# PATHOS_SOM_CAN.net
KiCad netlist of a schematic drawn in Altium Designer
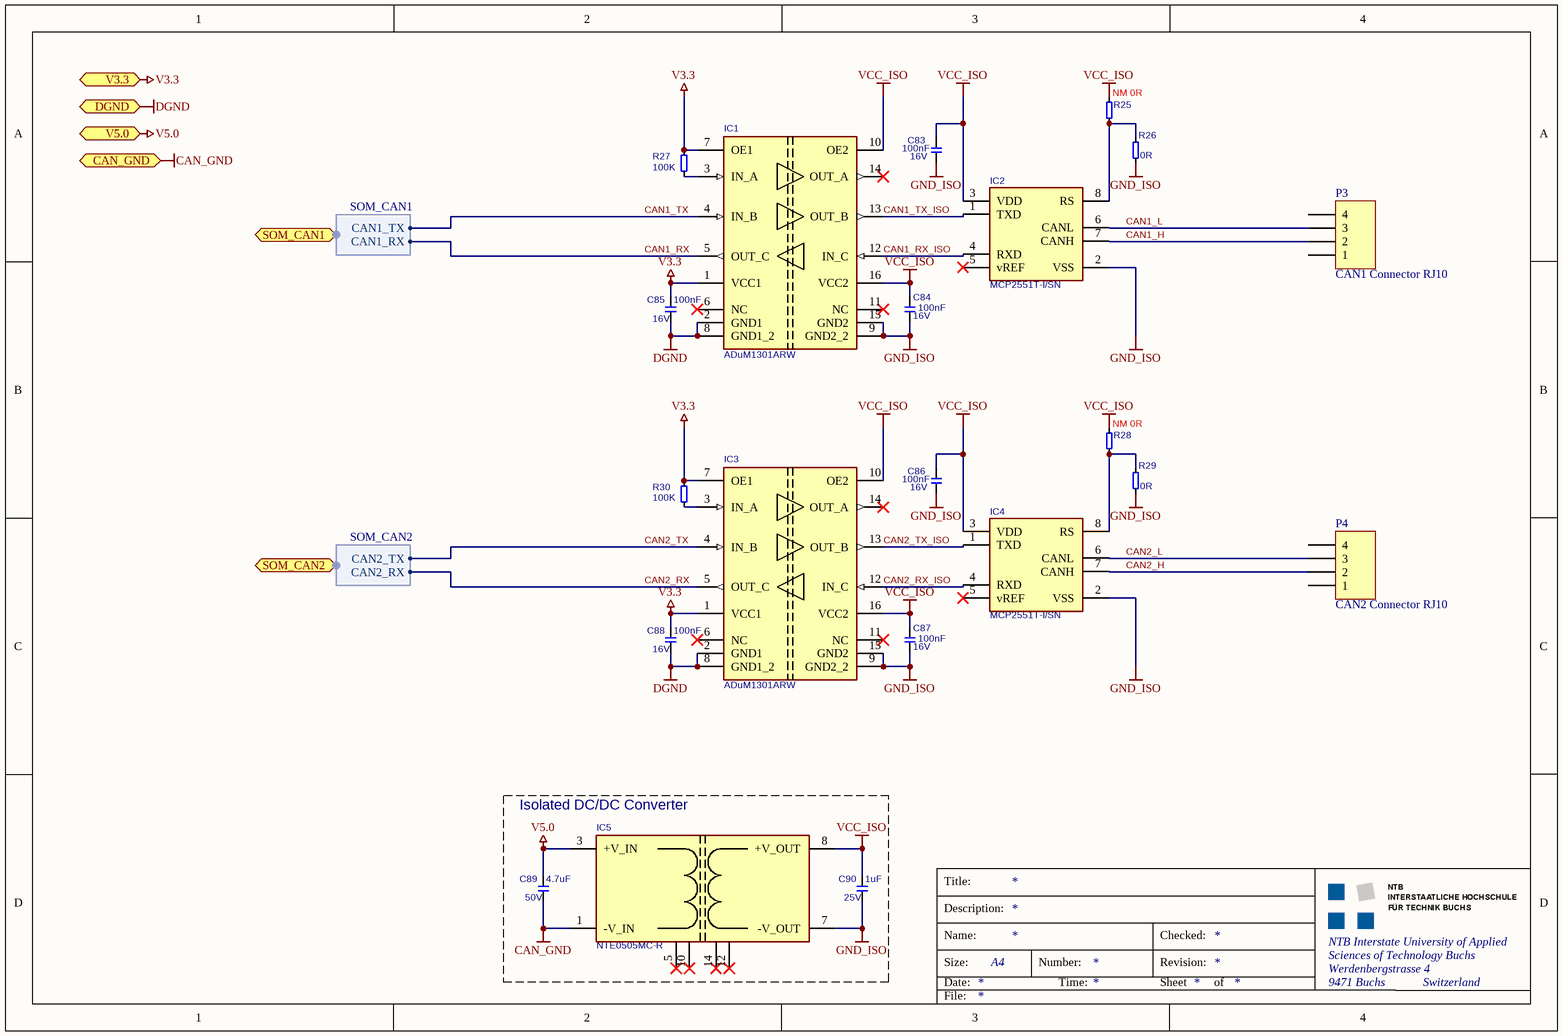
[diagram p0: PATHOS_SOM_CAN.SchDoc]

(export (version "E")
  (design (tool "Eeschema 10.0.6"))
  (components
    (comp (ref "C83")
      (value "100nF")
      (footprint "0603_3D")
      (description "Capacitor Ceramic X7R 100nF 16V 10% 0603")
      (fields (field (name "TOLERANCE") "10%") (field (name "RATING") "16V"))
      (libsource (lib "Evaluation Board") (part "C-X7R-100nF-16V-10%-0603"))
    )
    (comp (ref "C84")
      (value "100nF")
      (footprint "0603_3D")
      (description "Capacitor Ceramic X7R 100nF 16V 10% 0603")
      (fields (field (name "TOLERANCE") "10%") (field (name "RATING") "16V"))
      (libsource (lib "Evaluation Board") (part "C-X7R-100nF-16V-10%-0603"))
    )
    (comp (ref "C85")
      (value "100nF")
      (footprint "0603_3D")
      (description "Capacitor Ceramic X7R 100nF 16V 10% 0603")
      (fields (field (name "TOLERANCE") "10%") (field (name "RATING") "16V"))
      (libsource (lib "Evaluation Board") (part "C-X7R-100nF-16V-10%-0603"))
    )
    (comp (ref "C86")
      (value "100nF")
      (footprint "0603_3D")
      (description "Capacitor Ceramic X7R 100nF 16V 10% 0603")
      (fields (field (name "TOLERANCE") "10%") (field (name "RATING") "16V"))
      (libsource (lib "Evaluation Board") (part "C-X7R-100nF-16V-10%-0603"))
    )
    (comp (ref "C87")
      (value "100nF")
      (footprint "0603_3D")
      (description "Capacitor Ceramic X7R 100nF 16V 10% 0603")
      (fields (field (name "TOLERANCE") "10%") (field (name "RATING") "16V"))
      (libsource (lib "Evaluation Board") (part "C-X7R-100nF-16V-10%-0603"))
    )
    (comp (ref "C88")
      (value "100nF")
      (footprint "0603_3D")
      (description "Capacitor Ceramic X7R 100nF 16V 10% 0603")
      (fields (field (name "TOLERANCE") "10%") (field (name "RATING") "16V"))
      (libsource (lib "Evaluation Board") (part "C-X7R-100nF-16V-10%-0603"))
    )
    (comp (ref "C89")
      (value "4.7uF")
      (footprint "1206")
      (description "Capacitor Ceramic X7R 100nF 16V 10% 0603")
      (fields (field (name "TOLERANCE") "10%") (field (name "RATING") "50V"))
      (libsource (lib "Evaluation Board") (part "C-X7R-100nF-16V-10%-0603"))
    )
    (comp (ref "C90")
      (value "1uF")
      (footprint "0603_3D")
      (description "Capacitor Ceramic X7R 100nF 16V 10% 0603")
      (fields (field (name "TOLERANCE") "10%") (field (name "RATING") "25V"))
      (libsource (lib "Evaluation Board") (part "C-X7R-100nF-16V-10%-0603"))
    )
    (comp (ref "IC1")
      (value "ADuM1301ARW")
      (footprint "T_AD_ADuM1300ARW")
      (description "Digital Isolator")
      (fields (field (name "MANUFACTURER PART NO.") "ADuM1301ARW"))
      (libsource (lib "Evaluation Board") (part "IC-AD-ADuM1301ARW"))
    )
    (comp (ref "IC2")
      (value "MCP2551T-I/SN")
      (footprint "SOIC127P600X173-8N")
      (description "High speed CAN Transceiver")
      (fields (field (name "MANUFACTURER PART NO.") "MCP2551T-I/SN"))
      (libsource (lib "Evaluation Board") (part "IC-MC-MCP2551T-I/SN"))
    )
    (comp (ref "IC3")
      (value "ADuM1301ARW")
      (footprint "T_AD_ADuM1300ARW")
      (description "Digital Isolator")
      (fields (field (name "MANUFACTURER PART NO.") "ADuM1301ARW"))
      (libsource (lib "Evaluation Board") (part "IC-AD-ADuM1301ARW"))
    )
    (comp (ref "IC4")
      (value "MCP2551T-I/SN")
      (footprint "SOIC127P600X173-8N")
      (description "High speed CAN Transceiver")
      (fields (field (name "MANUFACTURER PART NO.") "MCP2551T-I/SN"))
      (libsource (lib "Evaluation Board") (part "IC-MC-MCP2551T-I/SN"))
    )
    (comp (ref "IC5")
      (value "NTE0505MC-R")
      (footprint "T_MURATA_NTE0505MC-R")
      (description "Isolated DC/DC Converter")
      (fields (field (name "MANUFACTURER PART NO.") "NTE0505MC-R"))
      (libsource (lib "Evaluation Board") (part "IC-MUR-NTE0505MC-R"))
    )
    (comp (ref "P3")
      (value "CAN1 Connector RJ10")
      (footprint "95009-2447")
      (description "Header, 4-Pin")
      (fields (field (name "PUBLISHER") "Altium Limited"))
      (libsource (lib "Miscellaneous Connectors") (part "Header 4"))
    )
    (comp (ref "P4")
      (value "CAN2 Connector RJ10")
      (footprint "95009-2447")
      (description "Header, 4-Pin")
      (fields (field (name "PUBLISHER") "Altium Limited"))
      (libsource (lib "Miscellaneous Connectors") (part "Header 4"))
    )
    (comp (ref "R25")
      (value "NM 0R")
      (footprint "0603_3D")
      (description "Resistor 0 ohm 63mW 1% 0603")
      (fields (field (name "TOLERANCE") "1%"))
      (libsource (lib "Evaluation Board") (part "R-0R-63mW-1%-0603"))
    )
    (comp (ref "R26")
      (value "0R")
      (footprint "0603_3D")
      (description "Resistor 0 ohm 63mW 1% 0603")
      (fields (field (name "TOLERANCE") "1%"))
      (libsource (lib "Evaluation Board") (part "R-0R-63mW-1%-0603"))
    )
    (comp (ref "R27")
      (value "100K")
      (footprint "0603_3D")
      (description "Resistor 100 Kohm 63mW 5% 0603")
      (fields (field (name "TOLERANCE") "5%"))
      (libsource (lib "Evaluation Board") (part "R-100KR-63mW-5%-0603"))
    )
    (comp (ref "R28")
      (value "NM 0R")
      (footprint "0603_3D")
      (description "Resistor 0 ohm 63mW 1% 0603")
      (fields (field (name "TOLERANCE") "1%"))
      (libsource (lib "Evaluation Board") (part "R-0R-63mW-1%-0603"))
    )
    (comp (ref "R29")
      (value "0R")
      (footprint "0603_3D")
      (description "Resistor 0 ohm 63mW 1% 0603")
      (fields (field (name "TOLERANCE") "1%"))
      (libsource (lib "Evaluation Board") (part "R-0R-63mW-1%-0603"))
    )
    (comp (ref "R30")
      (value "100K")
      (footprint "0603_3D")
      (description "Resistor 100 Kohm 63mW 5% 0603")
      (fields (field (name "TOLERANCE") "5%"))
      (libsource (lib "Evaluation Board") (part "R-100KR-63mW-5%-0603"))
    )
  )
  (nets
    (net (code "3") (name "/CAN1_H") (class "Default")
      (node (ref "IC2") (pin "7") (pinfunction "CANH_7") (pintype "passive"))
      (node (ref "P3") (pin "2") (pinfunction "2_2") (pintype "passive"))
    )
    (net (code "4") (name "/CAN1_L") (class "Default")
      (node (ref "IC2") (pin "6") (pinfunction "CANL_6") (pintype "passive"))
      (node (ref "P3") (pin "3") (pinfunction "3_3") (pintype "passive"))
    )
    (net (code "5") (name "/CAN1_RX") (class "Default")
      (node (ref "IC1") (pin "5") (pinfunction "OUT_C_5") (pintype "output"))
    )
    (net (code "6") (name "/CAN1_RX_ISO") (class "Default")
      (node (ref "IC1") (pin "12") (pinfunction "IN_C_12") (pintype "input"))
      (node (ref "IC2") (pin "4") (pinfunction "RXD_4") (pintype "passive"))
    )
    (net (code "7") (name "/CAN1_TX") (class "Default")
      (node (ref "IC1") (pin "4") (pinfunction "IN_B_4") (pintype "input"))
    )
    (net (code "8") (name "/CAN1_TX_ISO") (class "Default")
      (node (ref "IC1") (pin "13") (pinfunction "OUT_B_13") (pintype "output"))
      (node (ref "IC2") (pin "1") (pinfunction "TXD_1") (pintype "passive"))
    )
    (net (code "9") (name "/CAN2_H") (class "Default")
      (node (ref "IC4") (pin "7") (pinfunction "CANH_7") (pintype "passive"))
      (node (ref "P4") (pin "2") (pinfunction "2_2") (pintype "passive"))
    )
    (net (code "10") (name "/CAN2_L") (class "Default")
      (node (ref "IC4") (pin "6") (pinfunction "CANL_6") (pintype "passive"))
      (node (ref "P4") (pin "3") (pinfunction "3_3") (pintype "passive"))
    )
    (net (code "11") (name "/CAN2_RX") (class "Default")
      (node (ref "IC3") (pin "5") (pinfunction "OUT_C_5") (pintype "output"))
    )
    (net (code "12") (name "/CAN2_RX_ISO") (class "Default")
      (node (ref "IC3") (pin "12") (pinfunction "IN_C_12") (pintype "input"))
      (node (ref "IC4") (pin "4") (pinfunction "RXD_4") (pintype "passive"))
    )
    (net (code "13") (name "/CAN2_TX") (class "Default")
      (node (ref "IC3") (pin "4") (pinfunction "IN_B_4") (pintype "input"))
    )
    (net (code "14") (name "/CAN2_TX_ISO") (class "Default")
      (node (ref "IC3") (pin "13") (pinfunction "OUT_B_13") (pintype "output"))
      (node (ref "IC4") (pin "1") (pinfunction "TXD_1") (pintype "passive"))
    )
    (net (code "17") (name "CAN_GND") (class "Default")
      (node (ref "C89") (pin "1") (pinfunction "1_1") (pintype "passive"))
      (node (ref "IC5") (pin "1") (pinfunction "-V_IN_1") (pintype "power_in"))
    )
    (net (code "18") (name "DGND") (class "Default")
      (node (ref "C85") (pin "1") (pinfunction "1_1") (pintype "passive"))
      (node (ref "C88") (pin "1") (pinfunction "1_1") (pintype "passive"))
      (node (ref "IC1") (pin "2") (pinfunction "GND1_2") (pintype "power_in"))
      (node (ref "IC1") (pin "8") (pinfunction "GND1_2_8") (pintype "power_in"))
      (node (ref "IC3") (pin "2") (pinfunction "GND1_2") (pintype "power_in"))
      (node (ref "IC3") (pin "8") (pinfunction "GND1_2_8") (pintype "power_in"))
    )
    (net (code "19") (name "GND_ISO") (class "Default")
      (node (ref "C83") (pin "1") (pinfunction "1_1") (pintype "passive"))
      (node (ref "C84") (pin "1") (pinfunction "1_1") (pintype "passive"))
      (node (ref "C86") (pin "1") (pinfunction "1_1") (pintype "passive"))
      (node (ref "C87") (pin "1") (pinfunction "1_1") (pintype "passive"))
      (node (ref "C90") (pin "1") (pinfunction "1_1") (pintype "passive"))
      (node (ref "IC1") (pin "15") (pinfunction "GND2_15") (pintype "power_in"))
      (node (ref "IC1") (pin "9") (pinfunction "GND2_2_9") (pintype "power_in"))
      (node (ref "IC2") (pin "2") (pinfunction "VSS_2") (pintype "passive"))
      (node (ref "IC3") (pin "15") (pinfunction "GND2_15") (pintype "power_in"))
      (node (ref "IC3") (pin "9") (pinfunction "GND2_2_9") (pintype "power_in"))
      (node (ref "IC4") (pin "2") (pinfunction "VSS_2") (pintype "passive"))
      (node (ref "IC5") (pin "7") (pinfunction "-V_OUT_7") (pintype "power_in"))
      (node (ref "R26") (pin "1") (pinfunction "1_1") (pintype "passive"))
      (node (ref "R29") (pin "1") (pinfunction "1_1") (pintype "passive"))
    )
    (net (code "20") (name "Net-(IC1-IN_A)") (class "Default")
      (node (ref "IC1") (pin "3") (pinfunction "IN_A_3") (pintype "input"))
      (node (ref "R27") (pin "1") (pinfunction "1_1") (pintype "passive"))
    )
    (net (code "21") (name "Net-(IC2-RS)") (class "Default")
      (node (ref "IC2") (pin "8") (pinfunction "RS_8") (pintype "passive"))
      (node (ref "R25") (pin "1") (pinfunction "1_1") (pintype "passive"))
      (node (ref "R26") (pin "2") (pinfunction "2_2") (pintype "passive"))
    )
    (net (code "22") (name "Net-(IC3-IN_A)") (class "Default")
      (node (ref "IC3") (pin "3") (pinfunction "IN_A_3") (pintype "input"))
      (node (ref "R30") (pin "1") (pinfunction "1_1") (pintype "passive"))
    )
    (net (code "23") (name "Net-(IC4-RS)") (class "Default")
      (node (ref "IC4") (pin "8") (pinfunction "RS_8") (pintype "passive"))
      (node (ref "R28") (pin "1") (pinfunction "1_1") (pintype "passive"))
      (node (ref "R29") (pin "2") (pinfunction "2_2") (pintype "passive"))
    )
    (net (code "24") (name "V3.3") (class "Default")
      (node (ref "C85") (pin "2") (pinfunction "2_2") (pintype "passive"))
      (node (ref "C88") (pin "2") (pinfunction "2_2") (pintype "passive"))
      (node (ref "IC1") (pin "1") (pinfunction "VCC1_1") (pintype "passive"))
      (node (ref "IC1") (pin "7") (pinfunction "OE1_7") (pintype "passive"))
      (node (ref "IC3") (pin "1") (pinfunction "VCC1_1") (pintype "passive"))
      (node (ref "IC3") (pin "7") (pinfunction "OE1_7") (pintype "passive"))
      (node (ref "R27") (pin "2") (pinfunction "2_2") (pintype "passive"))
      (node (ref "R30") (pin "2") (pinfunction "2_2") (pintype "passive"))
    )
    (net (code "25") (name "V5.0") (class "Default")
      (node (ref "C89") (pin "2") (pinfunction "2_2") (pintype "passive"))
      (node (ref "IC5") (pin "3") (pinfunction "+V_IN_3") (pintype "power_in"))
    )
    (net (code "26") (name "VCC_ISO") (class "Default")
      (node (ref "C83") (pin "2") (pinfunction "2_2") (pintype "passive"))
      (node (ref "C84") (pin "2") (pinfunction "2_2") (pintype "passive"))
      (node (ref "C86") (pin "2") (pinfunction "2_2") (pintype "passive"))
      (node (ref "C87") (pin "2") (pinfunction "2_2") (pintype "passive"))
      (node (ref "C90") (pin "2") (pinfunction "2_2") (pintype "passive"))
      (node (ref "IC1") (pin "10") (pinfunction "OE2_10") (pintype "passive"))
      (node (ref "IC1") (pin "16") (pinfunction "VCC2_16") (pintype "passive"))
      (node (ref "IC2") (pin "3") (pinfunction "VDD_3") (pintype "passive"))
      (node (ref "IC3") (pin "10") (pinfunction "OE2_10") (pintype "passive"))
      (node (ref "IC3") (pin "16") (pinfunction "VCC2_16") (pintype "passive"))
      (node (ref "IC4") (pin "3") (pinfunction "VDD_3") (pintype "passive"))
      (node (ref "IC5") (pin "8") (pinfunction "+V_OUT_8") (pintype "power_in"))
      (node (ref "R25") (pin "2") (pinfunction "2_2") (pintype "passive"))
      (node (ref "R28") (pin "2") (pinfunction "2_2") (pintype "passive"))
    )
    (net (code "27") (name "unconnected-(IC1-NC-Pad6)") (class "Default")
      (node (ref "IC1") (pin "6") (pinfunction "NC_6") (pintype "passive+no_connect"))
    )
    (net (code "28") (name "unconnected-(IC1-NC-Pad11)") (class "Default")
      (node (ref "IC1") (pin "11") (pinfunction "NC_11") (pintype "passive+no_connect"))
    )
    (net (code "29") (name "unconnected-(IC1-OUT_A-Pad14)") (class "Default")
      (node (ref "IC1") (pin "14") (pinfunction "OUT_A_14") (pintype "output+no_connect"))
    )
    (net (code "30") (name "unconnected-(IC2-vREF-Pad5)") (class "Default")
      (node (ref "IC2") (pin "5") (pinfunction "vREF_5") (pintype "passive+no_connect"))
    )
    (net (code "31") (name "unconnected-(IC3-NC-Pad6)") (class "Default")
      (node (ref "IC3") (pin "6") (pinfunction "NC_6") (pintype "passive+no_connect"))
    )
    (net (code "32") (name "unconnected-(IC3-NC-Pad11)") (class "Default")
      (node (ref "IC3") (pin "11") (pinfunction "NC_11") (pintype "passive+no_connect"))
    )
    (net (code "33") (name "unconnected-(IC3-OUT_A-Pad14)") (class "Default")
      (node (ref "IC3") (pin "14") (pinfunction "OUT_A_14") (pintype "output+no_connect"))
    )
    (net (code "34") (name "unconnected-(IC4-vREF-Pad5)") (class "Default")
      (node (ref "IC4") (pin "5") (pinfunction "vREF_5") (pintype "passive+no_connect"))
    )
    (net (code "35") (name "unconnected-(IC5-NC-Pad5)") (class "Default")
      (node (ref "IC5") (pin "5") (pinfunction "NC_5") (pintype "passive+no_connect"))
    )
    (net (code "36") (name "unconnected-(IC5-NC-Pad10)") (class "Default")
      (node (ref "IC5") (pin "10") (pinfunction "NC_10") (pintype "passive+no_connect"))
    )
    (net (code "37") (name "unconnected-(IC5-NC-Pad12)") (class "Default")
      (node (ref "IC5") (pin "12") (pinfunction "NC_12") (pintype "passive+no_connect"))
    )
    (net (code "38") (name "unconnected-(IC5-NC-Pad14)") (class "Default")
      (node (ref "IC5") (pin "14") (pinfunction "NC_14") (pintype "passive+no_connect"))
    )
    (net (code "39") (name "unconnected-(P3-Pad1)") (class "Default")
      (node (ref "P3") (pin "1") (pinfunction "1_1") (pintype "passive"))
    )
    (net (code "40") (name "unconnected-(P3-Pad4)") (class "Default")
      (node (ref "P3") (pin "4") (pinfunction "4_4") (pintype "passive"))
    )
    (net (code "41") (name "unconnected-(P4-Pad1)") (class "Default")
      (node (ref "P4") (pin "1") (pinfunction "1_1") (pintype "passive"))
    )
    (net (code "42") (name "unconnected-(P4-Pad4)") (class "Default")
      (node (ref "P4") (pin "4") (pinfunction "4_4") (pintype "passive"))
    )
  )
)
